# weatherpod.net
KiCad netlist of a schematic drawn in EAGLE
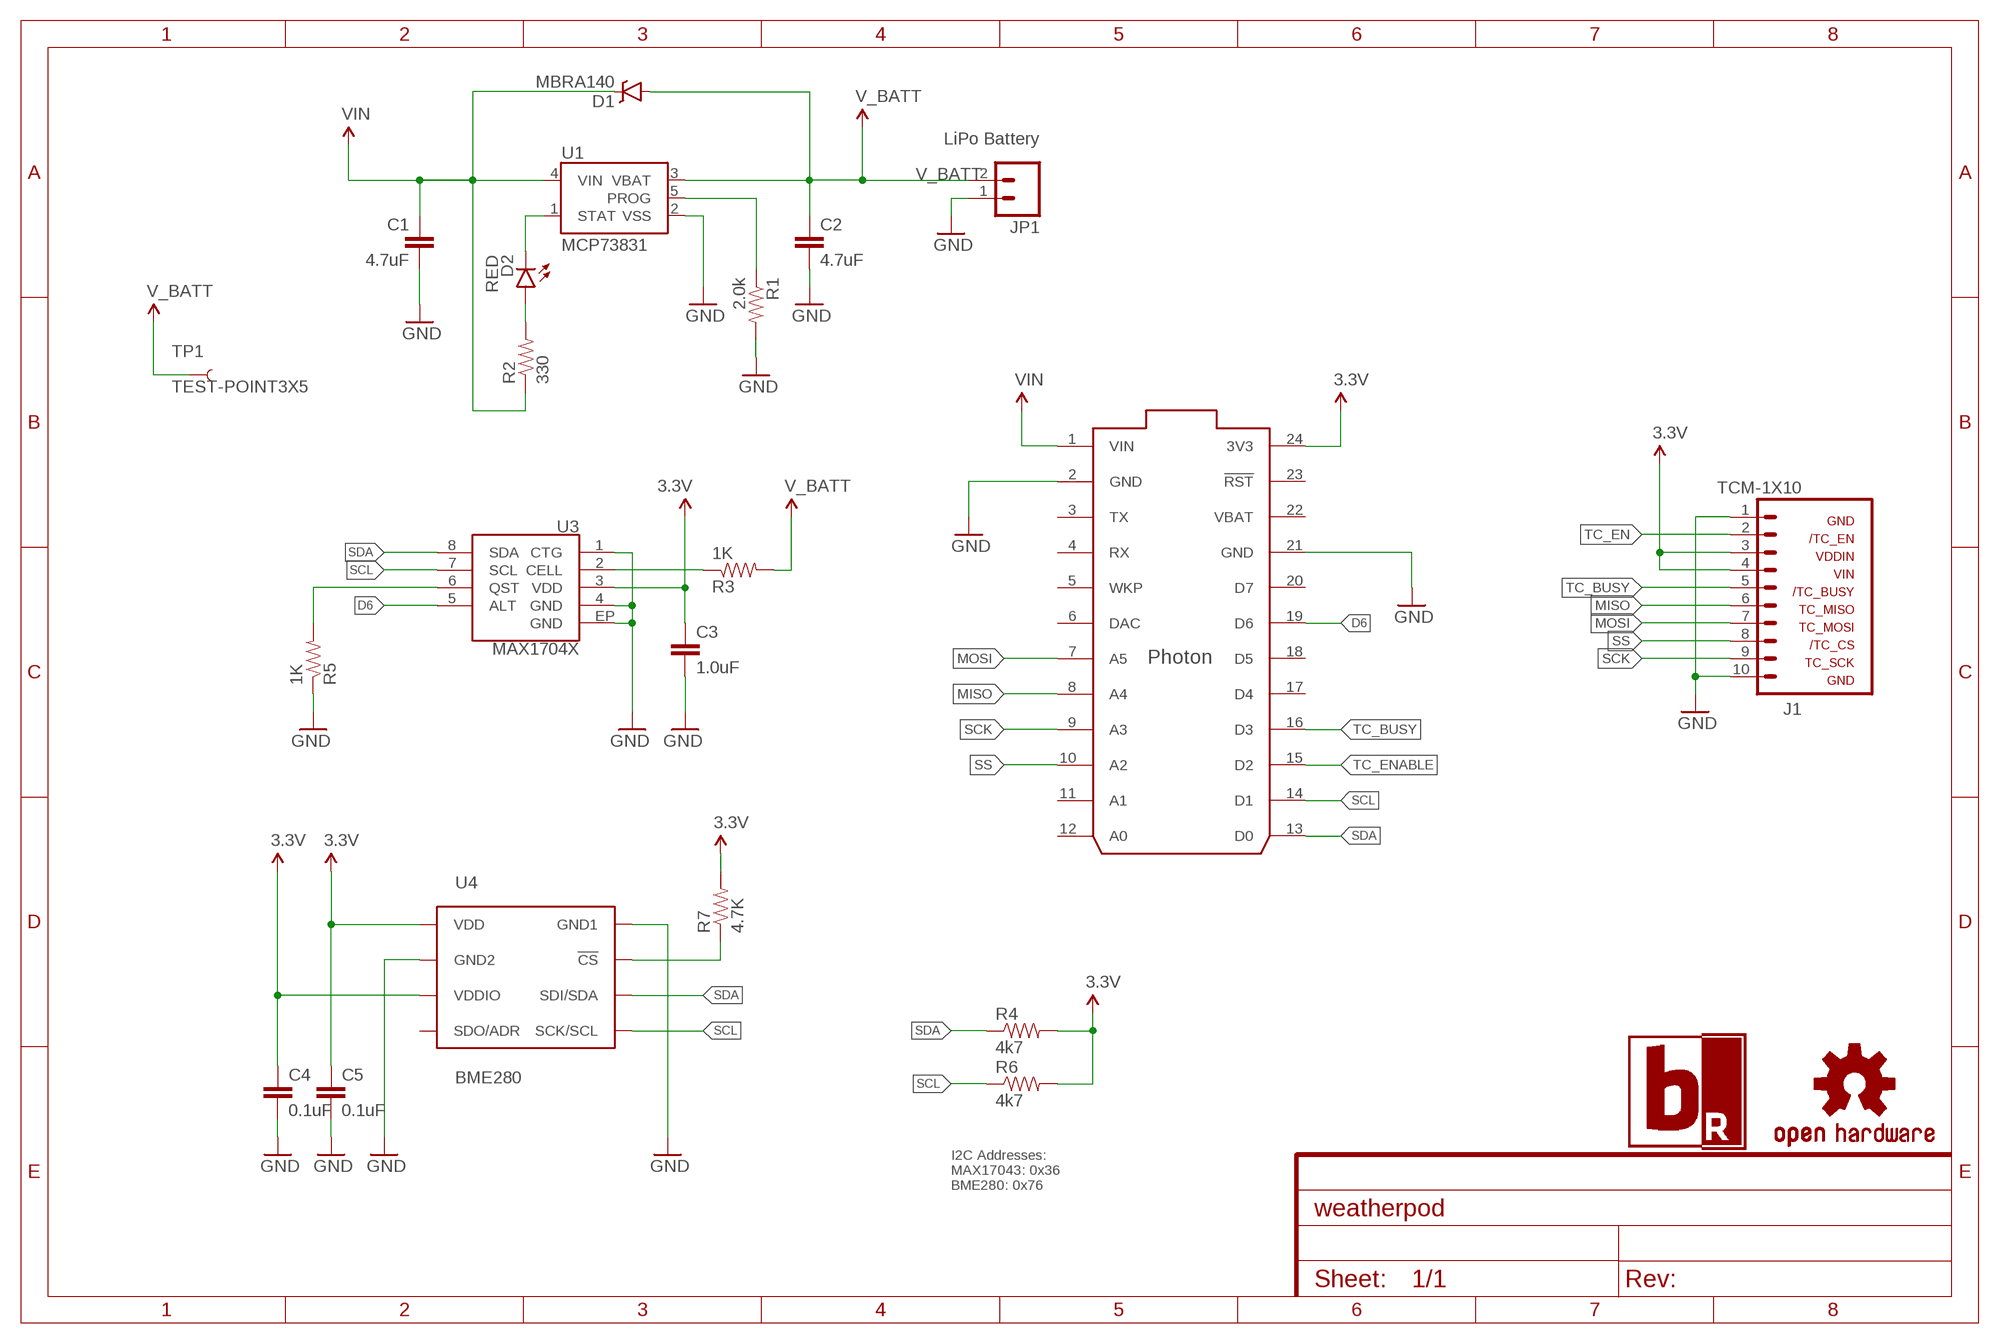
[diagram p0: schematic, sheet 1]

(export (version "E")
  (design (tool "Eeschema 10.0.6"))
  (components
    (comp (ref "C1")
      (value "4.7uF")
      (footprint "eagle-import:0603-CAP")
      (libsource (lib "eagle-import") (part "4.7UF-6.3V-10%(0603)0603"))
    )
    (comp (ref "C2")
      (value "4.7uF")
      (footprint "eagle-import:0603-CAP")
      (libsource (lib "eagle-import") (part "4.7UF-6.3V-10%(0603)0603"))
    )
    (comp (ref "C3")
      (value "1.0uF")
      (footprint "eagle-import:0603-CAP")
      (libsource (lib "eagle-import") (part "1.0UF-16V-10%(0603)"))
    )
    (comp (ref "C4")
      (value "0.1uF")
      (footprint "eagle-import:0603-CAP")
      (libsource (lib "eagle-import") (part "0.1UF-25V-5%(0603)"))
    )
    (comp (ref "C5")
      (value "0.1uF")
      (footprint "eagle-import:0603-CAP")
      (libsource (lib "eagle-import") (part "0.1UF-25V-5%(0603)"))
    )
    (comp (ref "D1")
      (value "MBRA140")
      (footprint "eagle-import:SMA-DIODE")
      (libsource (lib "eagle-import") (part "DIODE-SCHOTTKY-MBRA140"))
    )
    (comp (ref "D2")
      (value "RED")
      (footprint "eagle-import:LED-0603")
      (libsource (lib "eagle-import") (part "LED-RED0603"))
    )
    (comp (ref "J1")
      (value "TCM-1X10")
      (footprint "eagle-import:1X10")
      (libsource (lib "eagle-import") (part "TCM-1X10"))
    )
    (comp (ref "JP1")
      (value "M02-JST-2MM-SMT")
      (footprint "eagle-import:JST-2-SMD")
      (libsource (lib "eagle-import") (part "M02-JST-2MM-SMT"))
    )
    (comp (ref "LOGO1")
      (value "OSHW-LOGOS-COPPER")
      (footprint "eagle-import:OSHW-LOGO-S_COPPER")
      (libsource (lib "eagle-import") (part "OSHW-LOGOS-COPPER"))
    )
    (comp (ref "LOGO2")
      (value "BR-LOGO")
      (footprint "eagle-import:BR-LOGO-SMALL-COPPER")
      (libsource (lib "eagle-import") (part "BR-LOGO"))
    )
    (comp (ref "R1")
      (value "2.0k")
      (footprint "eagle-import:0603-RES")
      (libsource (lib "eagle-import") (part "2.0KOHM1/10W5%(0603)"))
    )
    (comp (ref "R2")
      (value "330")
      (footprint "eagle-import:0603-RES")
      (libsource (lib "eagle-import") (part "330OHM1/10W1%(0603)"))
    )
    (comp (ref "R3")
      (value "1K")
      (footprint "eagle-import:0603-RES")
      (libsource (lib "eagle-import") (part "1KOHM-1/10W-1%(0603)"))
    )
    (comp (ref "R4")
      (value "4k7")
      (footprint "eagle-import:0603-RES")
      (libsource (lib "eagle-import") (part "10KOHM-1/10W-1%(0603)0603"))
    )
    (comp (ref "R5")
      (value "1K")
      (footprint "eagle-import:0603-RES")
      (libsource (lib "eagle-import") (part "1KOHM-1/10W-1%(0603)"))
    )
    (comp (ref "R6")
      (value "4k7")
      (footprint "eagle-import:0603-RES")
      (libsource (lib "eagle-import") (part "10KOHM-1/10W-1%(0603)0603"))
    )
    (comp (ref "R7")
      (value "4.7K")
      (footprint "eagle-import:0603-RES")
      (libsource (lib "eagle-import") (part "4.7KOHM-1/10W-1%(0603)"))
    )
    (comp (ref "TP1")
      (value "TEST-POINT3X5")
      (footprint "eagle-import:PAD.03X.05")
      (libsource (lib "eagle-import") (part "TEST-POINT3X5"))
    )
    (comp (ref "U1")
      (value "MCP73831")
      (footprint "eagle-import:SOT23-5")
      (libsource (lib "eagle-import") (part "MCP73831"))
    )
    (comp (ref "U2")
      (value "PHOTON_SMD")
      (footprint "eagle-import:PHOTON_SMD")
      (libsource (lib "eagle-import") (part "PHOTON_SMD"))
    )
    (comp (ref "U3")
      (value "MAX1704X")
      (footprint "eagle-import:TDFN-8")
      (libsource (lib "eagle-import") (part "MAX1704X"))
    )
    (comp (ref "U4")
      (value "BME280")
      (footprint "eagle-import:BME280_LGA")
      (libsource (lib "eagle-import") (part "BME280"))
    )
  )
  (nets
    (net (code "1") (name "/VBAT") (class "Default")
      (node (ref "U2") (pin "22") (pinfunction "VBAT_22") (pintype "power_in"))
    )
    (net (code "2") (name "3.3V") (class "Default")
      (node (ref "C3") (pin "1") (pinfunction "1_1") (pintype "passive"))
      (node (ref "C4") (pin "1") (pinfunction "1_1") (pintype "passive"))
      (node (ref "C5") (pin "1") (pinfunction "1_1") (pintype "passive"))
      (node (ref "J1") (pin "3") (pinfunction "3_3") (pintype "power_in"))
      (node (ref "J1") (pin "4") (pinfunction "4_4") (pintype "power_in"))
      (node (ref "R4") (pin "2") (pinfunction "2_2") (pintype "passive"))
      (node (ref "R6") (pin "2") (pinfunction "2_2") (pintype "passive"))
      (node (ref "R7") (pin "2") (pinfunction "2_2") (pintype "passive"))
      (node (ref "U2") (pin "24") (pinfunction "3V3_24") (pintype "power_in"))
      (node (ref "U3") (pin "3") (pinfunction "VDD_3") (pintype "bidirectional"))
      (node (ref "U4") (pin "P$6") (pinfunction "VDDIO_P$6") (pintype "bidirectional"))
      (node (ref "U4") (pin "P$8") (pinfunction "VDD_P$8") (pintype "bidirectional"))
    )
    (net (code "3") (name "D6") (class "Default")
      (node (ref "U2") (pin "19") (pinfunction "D6_19") (pintype "bidirectional"))
      (node (ref "U3") (pin "5") (pinfunction "ALT_5") (pintype "bidirectional"))
    )
    (net (code "4") (name "GND") (class "Default")
      (node (ref "C1") (pin "2") (pinfunction "2_2") (pintype "passive"))
      (node (ref "C2") (pin "2") (pinfunction "2_2") (pintype "passive"))
      (node (ref "C3") (pin "2") (pinfunction "2_2") (pintype "passive"))
      (node (ref "C4") (pin "2") (pinfunction "2_2") (pintype "passive"))
      (node (ref "C5") (pin "2") (pinfunction "2_2") (pintype "passive"))
      (node (ref "J1") (pin "1") (pinfunction "1_1") (pintype "power_in"))
      (node (ref "J1") (pin "10") (pinfunction "10_10") (pintype "power_in"))
      (node (ref "JP1") (pin "1") (pinfunction "2_1") (pintype "passive"))
      (node (ref "R1") (pin "2") (pinfunction "2_2") (pintype "passive"))
      (node (ref "R5") (pin "1") (pinfunction "1_1") (pintype "passive"))
      (node (ref "U1") (pin "2") (pinfunction "VSS_2") (pintype "power_in"))
      (node (ref "U2") (pin "2") (pinfunction "GND_2") (pintype "power_in"))
      (node (ref "U2") (pin "21") (pinfunction "GND_21") (pintype "power_in"))
      (node (ref "U3") (pin "1") (pinfunction "CTG_1") (pintype "bidirectional"))
      (node (ref "U3") (pin "4") (pinfunction "GND_4") (pintype "bidirectional"))
      (node (ref "U3") (pin "EP") (pinfunction "GND_EP") (pintype "bidirectional"))
      (node (ref "U4") (pin "P$1") (pinfunction "GND1_P$1") (pintype "bidirectional"))
      (node (ref "U4") (pin "P$7") (pinfunction "GND2_P$7") (pintype "bidirectional"))
    )
    (net (code "5") (name "MISO") (class "Default")
      (node (ref "J1") (pin "6") (pinfunction "6_6") (pintype "output"))
      (node (ref "U2") (pin "8") (pinfunction "A4_8") (pintype "bidirectional"))
    )
    (net (code "6") (name "MOSI") (class "Default")
      (node (ref "J1") (pin "7") (pinfunction "7_7") (pintype "input"))
      (node (ref "U2") (pin "7") (pinfunction "A5_7") (pintype "bidirectional"))
    )
    (net (code "7") (name "Net-(D2-PadA)") (class "Default")
      (node (ref "D2") (pin "A") (pinfunction "A_A") (pintype "passive"))
      (node (ref "R2") (pin "2") (pinfunction "2_2") (pintype "passive"))
    )
    (net (code "8") (name "Net-(U1-PROG)") (class "Default")
      (node (ref "R1") (pin "1") (pinfunction "1_1") (pintype "passive"))
      (node (ref "U1") (pin "5") (pinfunction "PROG_5") (pintype "input"))
    )
    (net (code "9") (name "Net-(U1-STAT)") (class "Default")
      (node (ref "D2") (pin "C") (pinfunction "C_C") (pintype "passive"))
      (node (ref "U1") (pin "1") (pinfunction "STAT_1") (pintype "output"))
    )
    (net (code "10") (name "Net-(U3-CELL)") (class "Default")
      (node (ref "R3") (pin "1") (pinfunction "1_1") (pintype "passive"))
      (node (ref "U3") (pin "2") (pinfunction "CELL_2") (pintype "bidirectional"))
    )
    (net (code "11") (name "Net-(U3-QST)") (class "Default")
      (node (ref "R5") (pin "2") (pinfunction "2_2") (pintype "passive"))
      (node (ref "U3") (pin "6") (pinfunction "QST_6") (pintype "bidirectional"))
    )
    (net (code "12") (name "Net-(U4-~{CS})") (class "Default")
      (node (ref "R7") (pin "1") (pinfunction "1_1") (pintype "passive"))
      (node (ref "U4") (pin "P$2") (pinfunction "~{CS}_P$2") (pintype "bidirectional"))
    )
    (net (code "13") (name "SCK") (class "Default")
      (node (ref "J1") (pin "9") (pinfunction "9_9") (pintype "input"))
      (node (ref "U2") (pin "9") (pinfunction "A3_9") (pintype "bidirectional"))
    )
    (net (code "14") (name "SCL") (class "Default")
      (node (ref "R6") (pin "1") (pinfunction "1_1") (pintype "passive"))
      (node (ref "U2") (pin "14") (pinfunction "D1_14") (pintype "bidirectional"))
      (node (ref "U3") (pin "7") (pinfunction "SCL_7") (pintype "bidirectional"))
      (node (ref "U4") (pin "P$4") (pinfunction "SCK/SCL_P$4") (pintype "bidirectional"))
    )
    (net (code "15") (name "SDA") (class "Default")
      (node (ref "R4") (pin "1") (pinfunction "1_1") (pintype "passive"))
      (node (ref "U2") (pin "13") (pinfunction "D0_13") (pintype "bidirectional"))
      (node (ref "U3") (pin "8") (pinfunction "SDA_8") (pintype "bidirectional"))
      (node (ref "U4") (pin "P$3") (pinfunction "SDI/SDA_P$3") (pintype "bidirectional"))
    )
    (net (code "16") (name "SS") (class "Default")
      (node (ref "J1") (pin "8") (pinfunction "8_8") (pintype "input"))
      (node (ref "U2") (pin "10") (pinfunction "A2_10") (pintype "bidirectional"))
    )
    (net (code "17") (name "TC_BUSY") (class "Default")
      (node (ref "J1") (pin "5") (pinfunction "5_5") (pintype "output"))
      (node (ref "U2") (pin "16") (pinfunction "D3_16") (pintype "bidirectional"))
    )
    (net (code "18") (name "TC_EN") (class "Default")
      (node (ref "J1") (pin "2") (pinfunction "2_2") (pintype "input"))
    )
    (net (code "19") (name "TC_ENABLE") (class "Default")
      (node (ref "U2") (pin "15") (pinfunction "D2_15") (pintype "bidirectional"))
    )
    (net (code "20") (name "VIN") (class "Default")
      (node (ref "C1") (pin "1") (pinfunction "1_1") (pintype "passive"))
      (node (ref "D1") (pin "C") (pinfunction "C_C") (pintype "passive"))
      (node (ref "R2") (pin "1") (pinfunction "1_1") (pintype "passive"))
      (node (ref "U1") (pin "4") (pinfunction "VIN_4") (pintype "power_in"))
      (node (ref "U2") (pin "1") (pinfunction "VIN_1") (pintype "power_in"))
    )
    (net (code "21") (name "V_BATT") (class "Default")
      (node (ref "C2") (pin "1") (pinfunction "1_1") (pintype "passive"))
      (node (ref "D1") (pin "A") (pinfunction "A_A") (pintype "passive"))
      (node (ref "JP1") (pin "2") (pinfunction "1_2") (pintype "passive"))
      (node (ref "R3") (pin "2") (pinfunction "2_2") (pintype "passive"))
      (node (ref "TP1") (pin "P$1") (pinfunction "1_P$1") (pintype "bidirectional"))
      (node (ref "U1") (pin "3") (pinfunction "VBAT_3") (pintype "power_in"))
    )
    (net (code "22") (name "unconnected-(U2A-A0-Pad12)") (class "Default")
      (node (ref "U2") (pin "12") (pinfunction "A0_12") (pintype "bidirectional"))
    )
    (net (code "23") (name "unconnected-(U2A-A1-Pad11)") (class "Default")
      (node (ref "U2") (pin "11") (pinfunction "A1_11") (pintype "bidirectional"))
    )
    (net (code "24") (name "unconnected-(U2A-D4-Pad17)") (class "Default")
      (node (ref "U2") (pin "17") (pinfunction "D4_17") (pintype "bidirectional"))
    )
    (net (code "25") (name "unconnected-(U2A-D5-Pad18)") (class "Default")
      (node (ref "U2") (pin "18") (pinfunction "D5_18") (pintype "bidirectional"))
    )
    (net (code "26") (name "unconnected-(U2A-D7-Pad20)") (class "Default")
      (node (ref "U2") (pin "20") (pinfunction "D7_20") (pintype "bidirectional"))
    )
    (net (code "27") (name "unconnected-(U2A-DAC-Pad6)") (class "Default")
      (node (ref "U2") (pin "6") (pinfunction "DAC_6") (pintype "bidirectional"))
    )
    (net (code "28") (name "unconnected-(U2A-RX-Pad4)") (class "Default")
      (node (ref "U2") (pin "4") (pinfunction "RX_4") (pintype "bidirectional"))
    )
    (net (code "29") (name "unconnected-(U2A-TX-Pad3)") (class "Default")
      (node (ref "U2") (pin "3") (pinfunction "TX_3") (pintype "bidirectional"))
    )
    (net (code "30") (name "unconnected-(U2A-WKP-Pad5)") (class "Default")
      (node (ref "U2") (pin "5") (pinfunction "WKP_5") (pintype "bidirectional"))
    )
    (net (code "31") (name "unconnected-(U2A-~{RST}-Pad23)") (class "Default")
      (node (ref "U2") (pin "23") (pinfunction "~{RST}_23") (pintype "bidirectional"))
    )
    (net (code "32") (name "unconnected-(U4-SDO{slash}ADR-PadP$5)") (class "Default")
      (node (ref "U4") (pin "P$5") (pinfunction "SDO/ADR_P$5") (pintype "bidirectional"))
    )
  )
)
